# Eurorack_mini_psu.net
KiCad netlist of a schematic drawn in EAGLE
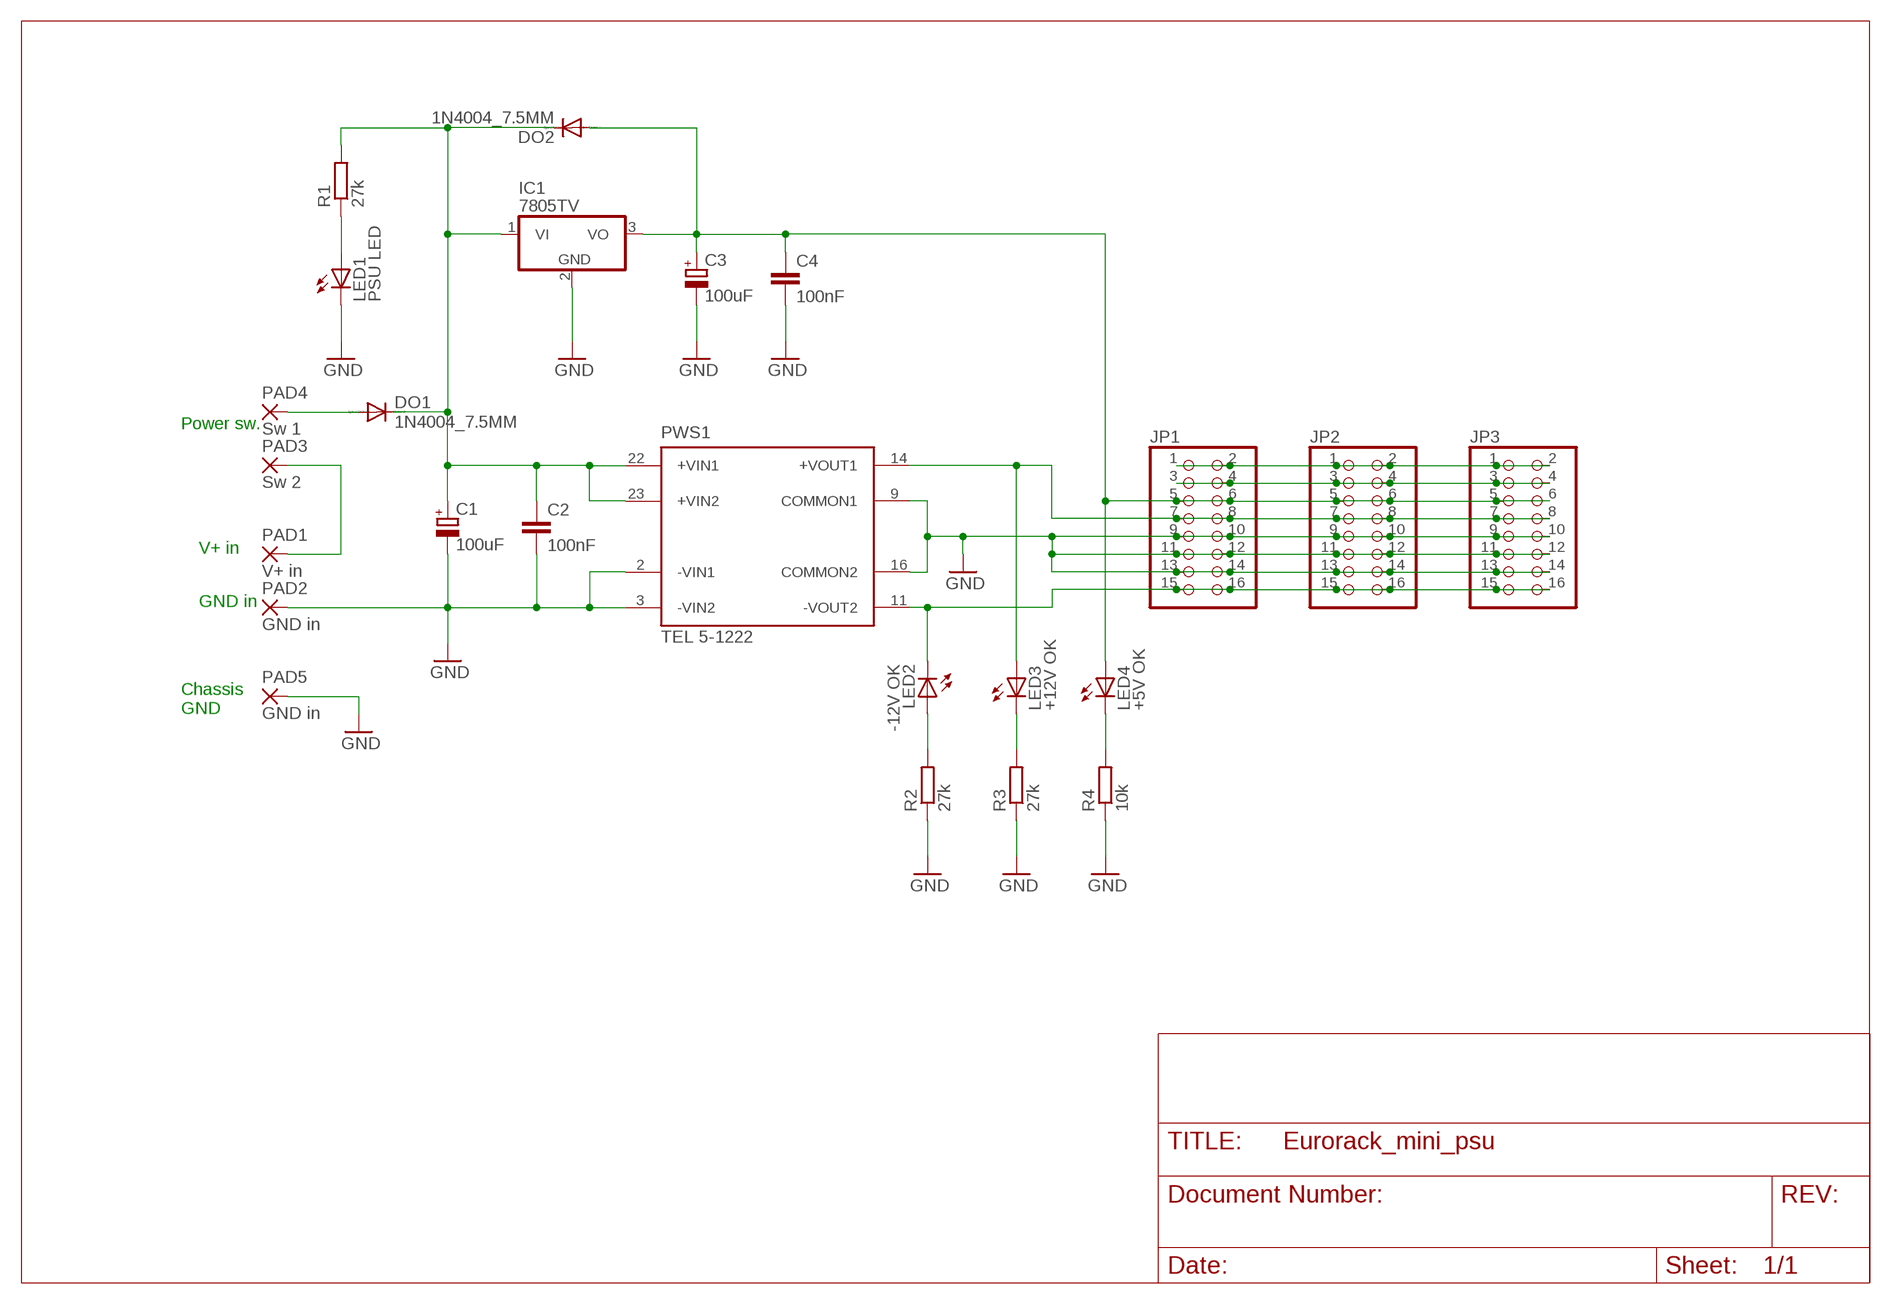
[diagram p0: schematic, sheet 1]

(export (version "E")
  (design (tool "Eeschema 10.0.6"))
  (components
    (comp (ref "C1")
      (value "100uF")
      (footprint "eagle-import:E2,5-6")
      (libsource (lib "eagle-import") (part "CPOL-EUE2.5-6"))
    )
    (comp (ref "C2")
      (value "100nF")
      (footprint "eagle-import:C025-025X050")
      (libsource (lib "eagle-import") (part "C-EU025-025X050"))
    )
    (comp (ref "C3")
      (value "100uF")
      (footprint "eagle-import:E2,5-6")
      (libsource (lib "eagle-import") (part "CPOL-EUE2.5-6"))
    )
    (comp (ref "C4")
      (value "100nF")
      (footprint "eagle-import:C025-025X050")
      (libsource (lib "eagle-import") (part "C-EU025-025X050"))
    )
    (comp (ref "DO1")
      (value "1N4004_7.5MM")
      (footprint "eagle-import:DO41-7")
      (libsource (lib "eagle-import") (part "1N4004_7.5MM"))
    )
    (comp (ref "DO2")
      (value "1N4004_7.5MM")
      (footprint "eagle-import:DO41-7")
      (libsource (lib "eagle-import") (part "1N4004_7.5MM"))
    )
    (comp (ref "IC1")
      (value "7805TV")
      (footprint "eagle-import:TO220V")
      (libsource (lib "eagle-import") (part "78TV05"))
    )
    (comp (ref "JP1")
      (value "PINHD-2X8")
      (footprint "eagle-import:2X08")
      (libsource (lib "eagle-import") (part "PINHD-2X8"))
    )
    (comp (ref "JP2")
      (value "PINHD-2X8")
      (footprint "eagle-import:2X08")
      (libsource (lib "eagle-import") (part "PINHD-2X8"))
    )
    (comp (ref "JP3")
      (value "PINHD-2X8")
      (footprint "eagle-import:2X08")
      (libsource (lib "eagle-import") (part "PINHD-2X8"))
    )
    (comp (ref "LED1")
      (value "PSU LED")
      (footprint "eagle-import:LED3MM")
      (libsource (lib "eagle-import") (part "LED3MM"))
    )
    (comp (ref "LED2")
      (value "-12V OK")
      (footprint "eagle-import:LED3MM")
      (libsource (lib "eagle-import") (part "LED3MM"))
    )
    (comp (ref "LED3")
      (value "+12V OK")
      (footprint "eagle-import:LED3MM")
      (libsource (lib "eagle-import") (part "LED3MM"))
    )
    (comp (ref "LED4")
      (value "+5V OK")
      (footprint "eagle-import:LED3MM")
      (libsource (lib "eagle-import") (part "LED3MM"))
    )
    (comp (ref "PAD1")
      (value "V+ in")
      (footprint "eagle-import:2,15_1,0")
      (libsource (lib "eagle-import") (part "2,15/1,0"))
    )
    (comp (ref "PAD2")
      (value "GND in")
      (footprint "eagle-import:2,15_1,0")
      (libsource (lib "eagle-import") (part "2,15/1,0"))
    )
    (comp (ref "PAD3")
      (value "Sw 2")
      (footprint "eagle-import:2,15_1,0")
      (libsource (lib "eagle-import") (part "2,15/1,0"))
    )
    (comp (ref "PAD4")
      (value "Sw 1")
      (footprint "eagle-import:2,15_1,0")
      (libsource (lib "eagle-import") (part "2,15/1,0"))
    )
    (comp (ref "PAD5")
      (value "GND in")
      (footprint "eagle-import:2,15_1,0")
      (libsource (lib "eagle-import") (part "2,15/1,0"))
    )
    (comp (ref "PWS1")
      (value "TEL 5-1222")
      (footprint "eagle-import:TEN3XXXX")
      (libsource (lib "eagle-import") (part "TEN_3--1223"))
    )
    (comp (ref "R1")
      (value "27k")
      (footprint "eagle-import:0207_7")
      (libsource (lib "eagle-import") (part "R-EU_0207/7"))
    )
    (comp (ref "R2")
      (value "27k")
      (footprint "eagle-import:0207_7")
      (libsource (lib "eagle-import") (part "R-EU_0207/7"))
    )
    (comp (ref "R3")
      (value "27k")
      (footprint "eagle-import:0207_7")
      (libsource (lib "eagle-import") (part "R-EU_0207/7"))
    )
    (comp (ref "R4")
      (value "10k")
      (footprint "eagle-import:0207_7")
      (libsource (lib "eagle-import") (part "R-EU_0207/7"))
    )
  )
  (nets
    (net (code "1") (name "GND") (class "Default")
      (node (ref "C1") (pin "-") (pinfunction "-_-") (pintype "passive"))
      (node (ref "C2") (pin "2") (pinfunction "2_2") (pintype "passive"))
      (node (ref "C3") (pin "-") (pinfunction "-_-") (pintype "passive"))
      (node (ref "C4") (pin "2") (pinfunction "2_2") (pintype "passive"))
      (node (ref "IC1") (pin "2") (pinfunction "GND_2") (pintype "passive"))
      (node (ref "JP1") (pin "10") (pinfunction "10_10") (pintype "passive"))
      (node (ref "JP1") (pin "11") (pinfunction "11_11") (pintype "passive"))
      (node (ref "JP1") (pin "12") (pinfunction "12_12") (pintype "passive"))
      (node (ref "JP1") (pin "13") (pinfunction "13_13") (pintype "passive"))
      (node (ref "JP1") (pin "14") (pinfunction "14_14") (pintype "passive"))
      (node (ref "JP1") (pin "9") (pinfunction "9_9") (pintype "passive"))
      (node (ref "JP2") (pin "10") (pinfunction "10_10") (pintype "passive"))
      (node (ref "JP2") (pin "11") (pinfunction "11_11") (pintype "passive"))
      (node (ref "JP2") (pin "12") (pinfunction "12_12") (pintype "passive"))
      (node (ref "JP2") (pin "13") (pinfunction "13_13") (pintype "passive"))
      (node (ref "JP2") (pin "14") (pinfunction "14_14") (pintype "passive"))
      (node (ref "JP2") (pin "9") (pinfunction "9_9") (pintype "passive"))
      (node (ref "JP3") (pin "10") (pinfunction "10_10") (pintype "passive"))
      (node (ref "JP3") (pin "11") (pinfunction "11_11") (pintype "passive"))
      (node (ref "JP3") (pin "12") (pinfunction "12_12") (pintype "passive"))
      (node (ref "JP3") (pin "13") (pinfunction "13_13") (pintype "passive"))
      (node (ref "JP3") (pin "14") (pinfunction "14_14") (pintype "passive"))
      (node (ref "JP3") (pin "9") (pinfunction "9_9") (pintype "passive"))
      (node (ref "LED1") (pin "K") (pinfunction "C_K") (pintype "passive"))
      (node (ref "PAD2") (pin "1") (pinfunction "P_1") (pintype "passive"))
      (node (ref "PAD5") (pin "1") (pinfunction "P_1") (pintype "passive"))
      (node (ref "PWS1") (pin "16") (pinfunction "COMMON2_16") (pintype "passive"))
      (node (ref "PWS1") (pin "2") (pinfunction "-VIN1_2") (pintype "input"))
      (node (ref "PWS1") (pin "3") (pinfunction "-VIN2_3") (pintype "input"))
      (node (ref "PWS1") (pin "9") (pinfunction "COMMON1_9") (pintype "passive"))
      (node (ref "R2") (pin "1") (pinfunction "1_1") (pintype "passive"))
      (node (ref "R3") (pin "1") (pinfunction "1_1") (pintype "passive"))
      (node (ref "R4") (pin "1") (pinfunction "1_1") (pintype "passive"))
    )
    (net (code "2") (name "Net-(IC1-VI)") (class "Default")
      (node (ref "C1") (pin "+") (pinfunction "+_+") (pintype "passive"))
      (node (ref "C2") (pin "1") (pinfunction "1_1") (pintype "passive"))
      (node (ref "DO1") (pin "C") (pinfunction "C_C") (pintype "passive"))
      (node (ref "DO2") (pin "C") (pinfunction "C_C") (pintype "passive"))
      (node (ref "IC1") (pin "1") (pinfunction "VI_1") (pintype "input"))
      (node (ref "PWS1") (pin "22") (pinfunction "+VIN1_22") (pintype "input"))
      (node (ref "PWS1") (pin "23") (pinfunction "+VIN2_23") (pintype "input"))
      (node (ref "R1") (pin "2") (pinfunction "2_2") (pintype "passive"))
    )
    (net (code "3") (name "Net-(IC1-VO)") (class "Default")
      (node (ref "C3") (pin "+") (pinfunction "+_+") (pintype "passive"))
      (node (ref "C4") (pin "1") (pinfunction "1_1") (pintype "passive"))
      (node (ref "DO2") (pin "A") (pinfunction "A_A") (pintype "passive"))
      (node (ref "IC1") (pin "3") (pinfunction "VO_3") (pintype "passive"))
      (node (ref "JP1") (pin "5") (pinfunction "5_5") (pintype "passive"))
      (node (ref "JP1") (pin "6") (pinfunction "6_6") (pintype "passive"))
      (node (ref "JP2") (pin "5") (pinfunction "5_5") (pintype "passive"))
      (node (ref "JP2") (pin "6") (pinfunction "6_6") (pintype "passive"))
      (node (ref "JP3") (pin "5") (pinfunction "5_5") (pintype "passive"))
      (node (ref "JP3") (pin "6") (pinfunction "6_6") (pintype "passive"))
      (node (ref "LED4") (pin "A") (pinfunction "A_A") (pintype "passive"))
    )
    (net (code "4") (name "Net-(JP1-Pad1)") (class "Default")
      (node (ref "JP1") (pin "1") (pinfunction "1_1") (pintype "passive"))
      (node (ref "JP1") (pin "2") (pinfunction "2_2") (pintype "passive"))
      (node (ref "JP2") (pin "1") (pinfunction "1_1") (pintype "passive"))
      (node (ref "JP2") (pin "2") (pinfunction "2_2") (pintype "passive"))
      (node (ref "JP3") (pin "1") (pinfunction "1_1") (pintype "passive"))
      (node (ref "JP3") (pin "2") (pinfunction "2_2") (pintype "passive"))
    )
    (net (code "5") (name "Net-(JP1-Pad3)") (class "Default")
      (node (ref "JP1") (pin "3") (pinfunction "3_3") (pintype "passive"))
      (node (ref "JP1") (pin "4") (pinfunction "4_4") (pintype "passive"))
      (node (ref "JP2") (pin "3") (pinfunction "3_3") (pintype "passive"))
      (node (ref "JP2") (pin "4") (pinfunction "4_4") (pintype "passive"))
      (node (ref "JP3") (pin "3") (pinfunction "3_3") (pintype "passive"))
      (node (ref "JP3") (pin "4") (pinfunction "4_4") (pintype "passive"))
    )
    (net (code "6") (name "Net-(LED1-PadA)") (class "Default")
      (node (ref "LED1") (pin "A") (pinfunction "A_A") (pintype "passive"))
      (node (ref "R1") (pin "1") (pinfunction "1_1") (pintype "passive"))
    )
    (net (code "7") (name "Net-(LED2-C)") (class "Default")
      (node (ref "JP1") (pin "15") (pinfunction "15_15") (pintype "passive"))
      (node (ref "JP1") (pin "16") (pinfunction "16_16") (pintype "passive"))
      (node (ref "JP2") (pin "15") (pinfunction "15_15") (pintype "passive"))
      (node (ref "JP2") (pin "16") (pinfunction "16_16") (pintype "passive"))
      (node (ref "JP3") (pin "15") (pinfunction "15_15") (pintype "passive"))
      (node (ref "JP3") (pin "16") (pinfunction "16_16") (pintype "passive"))
      (node (ref "LED2") (pin "K") (pinfunction "C_K") (pintype "passive"))
      (node (ref "PWS1") (pin "11") (pinfunction "-VOUT2_11") (pintype "passive"))
    )
    (net (code "8") (name "Net-(LED2-PadA)") (class "Default")
      (node (ref "LED2") (pin "A") (pinfunction "A_A") (pintype "passive"))
      (node (ref "R2") (pin "2") (pinfunction "2_2") (pintype "passive"))
    )
    (net (code "9") (name "Net-(LED3-C)") (class "Default")
      (node (ref "LED3") (pin "K") (pinfunction "C_K") (pintype "passive"))
      (node (ref "R3") (pin "2") (pinfunction "2_2") (pintype "passive"))
    )
    (net (code "10") (name "Net-(LED4-C)") (class "Default")
      (node (ref "LED4") (pin "K") (pinfunction "C_K") (pintype "passive"))
      (node (ref "R4") (pin "2") (pinfunction "2_2") (pintype "passive"))
    )
    (net (code "11") (name "Net-(PAD1-P)") (class "Default")
      (node (ref "PAD1") (pin "1") (pinfunction "P_1") (pintype "passive"))
      (node (ref "PAD3") (pin "1") (pinfunction "P_1") (pintype "passive"))
    )
    (net (code "12") (name "Net-(PAD4-P)") (class "Default")
      (node (ref "DO1") (pin "A") (pinfunction "A_A") (pintype "passive"))
      (node (ref "PAD4") (pin "1") (pinfunction "P_1") (pintype "passive"))
    )
    (net (code "13") (name "Net-(PWS1-+VOUT1)") (class "Default")
      (node (ref "JP1") (pin "7") (pinfunction "7_7") (pintype "passive"))
      (node (ref "JP1") (pin "8") (pinfunction "8_8") (pintype "passive"))
      (node (ref "JP2") (pin "7") (pinfunction "7_7") (pintype "passive"))
      (node (ref "JP2") (pin "8") (pinfunction "8_8") (pintype "passive"))
      (node (ref "JP3") (pin "7") (pinfunction "7_7") (pintype "passive"))
      (node (ref "JP3") (pin "8") (pinfunction "8_8") (pintype "passive"))
      (node (ref "LED3") (pin "A") (pinfunction "A_A") (pintype "passive"))
      (node (ref "PWS1") (pin "14") (pinfunction "+VOUT1_14") (pintype "passive"))
    )
  )
)
